# dac-ldo.net
KiCad netlist of a schematic drawn in Altium Designer
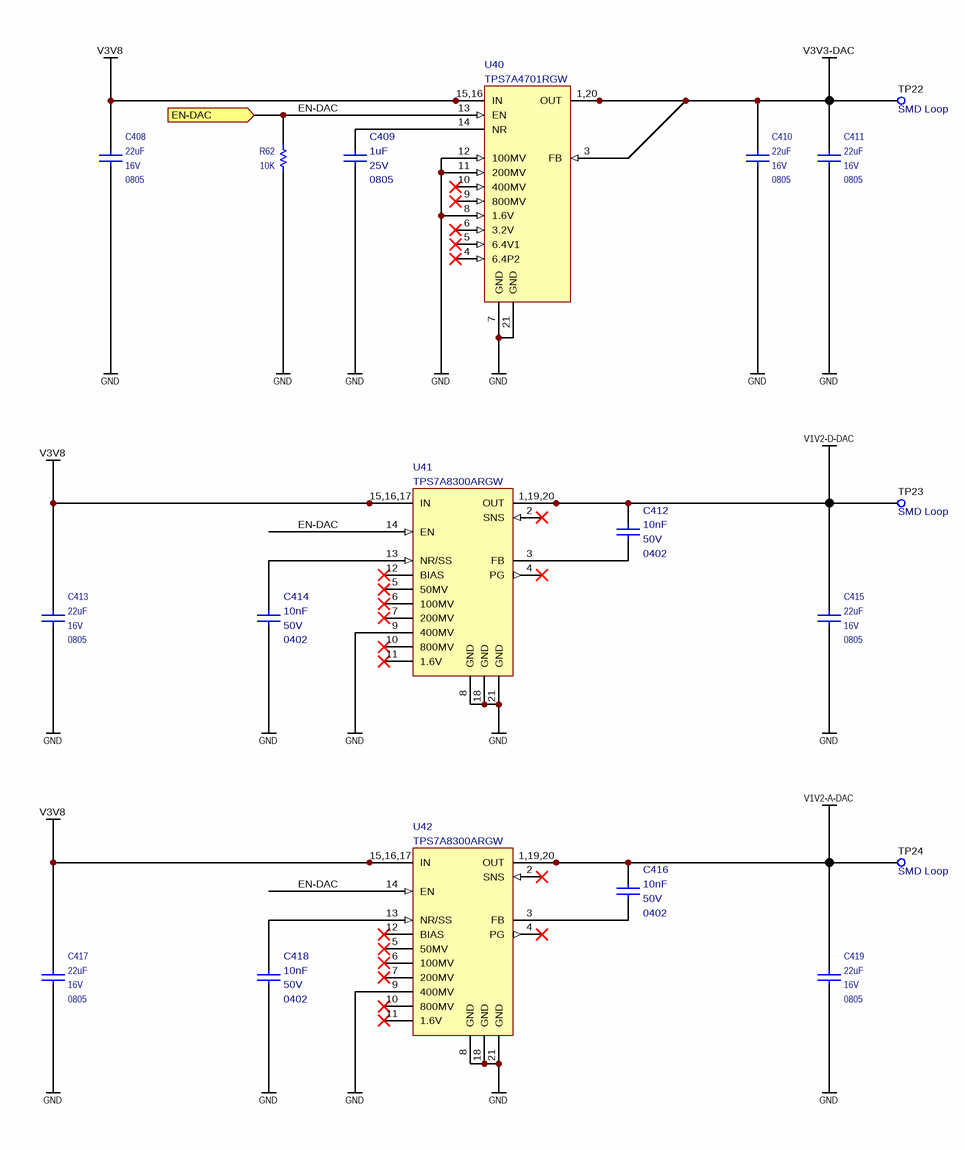
[diagram p0: dac-ldo.SchDoc]

(export (version "E")
  (design (tool "Eeschema 10.0.6"))
  (components
    (comp (ref "C408")
      (value "22uF")
      (footprint "generic:CAPC200X125X145L45N")
      (description "Ceramic Capacitor 22uF ±10% 16V X5R 0805")
      (fields
        (field (name "MANUFACTURER") "Samsung")
        (field (name "VOLTAGE") "16V")
        (field (name "PACKAGE") "0805")
        (field (name "TOLERANCE") "±10%")
      )
      (libsource (lib "generic") (part "CAP 0603"))
    )
    (comp (ref "C409")
      (value "1uF")
      (footprint "CAPC200X125X145L45N")
      (description "Ceramic Capacitor 1uF ±10% 25V X7R 0805")
      (fields
        (field (name "MANUFACTURER") "Taiyo Yuden")
        (field (name "TOLERANCE") "±10%")
        (field (name "PACKAGE") "0805")
        (field (name "VOLTAGE") "25V")
      )
      (libsource (lib "capacitors") (part "CAP"))
    )
    (comp (ref "C410")
      (value "22uF")
      (footprint "generic:CAPC200X125X145L45N")
      (description "Ceramic Capacitor 22uF ±10% 16V X5R 0805")
      (fields
        (field (name "MANUFACTURER") "Samsung")
        (field (name "VOLTAGE") "16V")
        (field (name "PACKAGE") "0805")
        (field (name "TOLERANCE") "±10%")
      )
      (libsource (lib "generic") (part "CAP 0603"))
    )
    (comp (ref "C411")
      (value "22uF")
      (footprint "generic:CAPC200X125X145L45N")
      (description "Ceramic Capacitor 22uF ±10% 16V X5R 0805")
      (fields
        (field (name "MANUFACTURER") "Samsung")
        (field (name "VOLTAGE") "16V")
        (field (name "PACKAGE") "0805")
        (field (name "TOLERANCE") "±10%")
      )
      (libsource (lib "generic") (part "CAP 0603"))
    )
    (comp (ref "C412")
      (value "10nF")
      (footprint "generic:CAPC100X50X55L25N")
      (description "Ceramic Capacitor 10nF ±10% 50V X7R 0402")
      (fields
        (field (name "MANUFACTURER") "Murata")
        (field (name "TOLERANCE") "±10%")
        (field (name "PACKAGE") "0402")
        (field (name "VOLTAGE") "50V")
      )
      (libsource (lib "capacitors") (part "CAP"))
    )
    (comp (ref "C413")
      (value "22uF")
      (footprint "generic:CAPC200X125X145L45N")
      (description "Ceramic Capacitor 22uF ±10% 16V X5R 0805")
      (fields
        (field (name "MANUFACTURER") "Samsung")
        (field (name "VOLTAGE") "16V")
        (field (name "PACKAGE") "0805")
        (field (name "TOLERANCE") "±10%")
      )
      (libsource (lib "generic") (part "CAP 0603"))
    )
    (comp (ref "C414")
      (value "10nF")
      (footprint "generic:CAPC100X50X55L25N")
      (description "Ceramic Capacitor 10nF ±10% 50V X7R 0402")
      (fields
        (field (name "MANUFACTURER") "Murata")
        (field (name "TOLERANCE") "±10%")
        (field (name "PACKAGE") "0402")
        (field (name "VOLTAGE") "50V")
      )
      (libsource (lib "capacitors") (part "CAP"))
    )
    (comp (ref "C415")
      (value "22uF")
      (footprint "generic:CAPC200X125X145L45N")
      (description "Ceramic Capacitor 22uF ±10% 16V X5R 0805")
      (fields
        (field (name "MANUFACTURER") "Samsung")
        (field (name "VOLTAGE") "16V")
        (field (name "PACKAGE") "0805")
        (field (name "TOLERANCE") "±10%")
      )
      (libsource (lib "generic") (part "CAP 0603"))
    )
    (comp (ref "C416")
      (value "10nF")
      (footprint "generic:CAPC100X50X55L25N")
      (description "Ceramic Capacitor 10nF ±10% 50V X7R 0402")
      (fields
        (field (name "MANUFACTURER") "Murata")
        (field (name "TOLERANCE") "±10%")
        (field (name "PACKAGE") "0402")
        (field (name "VOLTAGE") "50V")
      )
      (libsource (lib "capacitors") (part "CAP"))
    )
    (comp (ref "C417")
      (value "22uF")
      (footprint "generic:CAPC200X125X145L45N")
      (description "Ceramic Capacitor 22uF ±10% 16V X5R 0805")
      (fields
        (field (name "MANUFACTURER") "Samsung")
        (field (name "VOLTAGE") "16V")
        (field (name "PACKAGE") "0805")
        (field (name "TOLERANCE") "±10%")
      )
      (libsource (lib "generic") (part "CAP 0603"))
    )
    (comp (ref "C418")
      (value "10nF")
      (footprint "generic:CAPC100X50X55L25N")
      (description "Ceramic Capacitor 10nF ±10% 50V X7R 0402")
      (fields
        (field (name "MANUFACTURER") "Murata")
        (field (name "TOLERANCE") "±10%")
        (field (name "PACKAGE") "0402")
        (field (name "VOLTAGE") "50V")
      )
      (libsource (lib "capacitors") (part "CAP"))
    )
    (comp (ref "C419")
      (value "22uF")
      (footprint "generic:CAPC200X125X145L45N")
      (description "Ceramic Capacitor 22uF ±10% 16V X5R 0805")
      (fields
        (field (name "MANUFACTURER") "Samsung")
        (field (name "VOLTAGE") "16V")
        (field (name "PACKAGE") "0805")
        (field (name "TOLERANCE") "±10%")
      )
      (libsource (lib "generic") (part "CAP 0603"))
    )
    (comp (ref "R62")
      (value "10K")
      (footprint "RESC1005X40N")
      (description "Thick Film Resistor 10k ±1% 0.1W 50V 0402")
      (fields (field (name "MANUFACTURER") "Panasonic") (field (name "TOLERANCE") "±1%"))
      (libsource (lib "Graviton") (part "RES 0402"))
    )
    (comp (ref "TP22")
      (value "5015")
      (footprint "keystone:5015")
      (description "Test Point SMD")
      (fields (field (name "MANUFACTURER") "Keystone") (field (name "NOTES") "SMD Loop"))
      (libsource (lib "generic") (part "TEST_POINT_SMD_50"))
    )
    (comp (ref "TP23")
      (value "5015")
      (footprint "keystone:5015")
      (description "Test Point SMD")
      (fields (field (name "MANUFACTURER") "Keystone") (field (name "NOTES") "SMD Loop"))
      (libsource (lib "generic") (part "TEST_POINT_SMD_50"))
    )
    (comp (ref "TP24")
      (value "5015")
      (footprint "keystone:5015")
      (description "Test Point SMD")
      (fields (field (name "MANUFACTURER") "Keystone") (field (name "NOTES") "SMD Loop"))
      (libsource (lib "generic") (part "TEST_POINT_SMD_50"))
    )
    (comp (ref "U40")
      (value "TPS7A4701RGW")
      (footprint "QFN65P500X500X100-21N")
      (description "Low-Dropout Linear Regulator 20-VQFN")
      (fields (field (name "MANUFACTURER") "Texas Instruments"))
      (libsource (lib "ti") (part "TPS7A4701RGW_1"))
    )
    (comp (ref "U41")
      (value "TPS7A8300ARGW")
      (footprint "texas_instruments:QFN65P500X500X100-21N")
      (description "LDO Regulator, 2A, VQFN-20")
      (fields (field (name "MANUFACTURER") "Texas Instruments"))
      (libsource (lib "ti") (part "TPS7A8300ARGW"))
    )
    (comp (ref "U42")
      (value "TPS7A8300ARGW")
      (footprint "texas_instruments:QFN65P500X500X100-21N")
      (description "LDO Regulator, 2A, VQFN-20")
      (fields (field (name "MANUFACTURER") "Texas Instruments"))
      (libsource (lib "ti") (part "TPS7A8300ARGW"))
    )
  )
  (nets
    (net (code "1") (name "/EN-DAC") (class "Default")
      (node (ref "R62") (pin "1") (pinfunction "1_1") (pintype "passive"))
      (node (ref "U40") (pin "13") (pinfunction "EN_13") (pintype "input"))
      (node (ref "U41") (pin "14") (pinfunction "EN_14") (pintype "input"))
      (node (ref "U42") (pin "14") (pinfunction "EN_14") (pintype "input"))
    )
    (net (code "2") (name "GND") (class "Default")
      (node (ref "C408") (pin "1") (pinfunction "1_1") (pintype "passive"))
      (node (ref "C409") (pin "2") (pinfunction "2_2") (pintype "passive"))
      (node (ref "C410") (pin "1") (pinfunction "1_1") (pintype "passive"))
      (node (ref "C411") (pin "1") (pinfunction "1_1") (pintype "passive"))
      (node (ref "C413") (pin "1") (pinfunction "1_1") (pintype "passive"))
      (node (ref "C414") (pin "2") (pinfunction "2_2") (pintype "passive"))
      (node (ref "C415") (pin "1") (pinfunction "1_1") (pintype "passive"))
      (node (ref "C417") (pin "1") (pinfunction "1_1") (pintype "passive"))
      (node (ref "C418") (pin "2") (pinfunction "2_2") (pintype "passive"))
      (node (ref "C419") (pin "1") (pinfunction "1_1") (pintype "passive"))
      (node (ref "R62") (pin "2") (pinfunction "2_2") (pintype "passive"))
      (node (ref "U40") (pin "11") (pinfunction "200MV_11") (pintype "input"))
      (node (ref "U40") (pin "12") (pinfunction "100MV_12") (pintype "input"))
      (node (ref "U40") (pin "21") (pinfunction "GND_21") (pintype "power_in"))
      (node (ref "U40") (pin "7") (pinfunction "GND_7") (pintype "power_in"))
      (node (ref "U40") (pin "8") (pinfunction "1.6V_8") (pintype "input"))
      (node (ref "U41") (pin "18") (pinfunction "GND_18") (pintype "passive"))
      (node (ref "U41") (pin "21") (pinfunction "GND_21") (pintype "passive"))
      (node (ref "U41") (pin "8") (pinfunction "GND_8") (pintype "passive"))
      (node (ref "U41") (pin "9") (pinfunction "400MV_9") (pintype "passive"))
      (node (ref "U42") (pin "18") (pinfunction "GND_18") (pintype "passive"))
      (node (ref "U42") (pin "21") (pinfunction "GND_21") (pintype "passive"))
      (node (ref "U42") (pin "8") (pinfunction "GND_8") (pintype "passive"))
      (node (ref "U42") (pin "9") (pinfunction "400MV_9") (pintype "passive"))
    )
    (net (code "3") (name "Net-(U40-NR)") (class "Default")
      (node (ref "C409") (pin "1") (pinfunction "1_1") (pintype "passive"))
      (node (ref "U40") (pin "14") (pinfunction "NR_14") (pintype "passive"))
    )
    (net (code "4") (name "Net-(U41-FB)") (class "Default")
      (node (ref "C412") (pin "2") (pinfunction "2_2") (pintype "passive"))
      (node (ref "U41") (pin "3") (pinfunction "FB_3") (pintype "passive"))
    )
    (net (code "5") (name "Net-(U41-NR{slash}SS)") (class "Default")
      (node (ref "C414") (pin "1") (pinfunction "1_1") (pintype "passive"))
      (node (ref "U41") (pin "13") (pinfunction "NR/SS_13") (pintype "input"))
    )
    (net (code "6") (name "Net-(U42-FB)") (class "Default")
      (node (ref "C416") (pin "2") (pinfunction "2_2") (pintype "passive"))
      (node (ref "U42") (pin "3") (pinfunction "FB_3") (pintype "passive"))
    )
    (net (code "7") (name "Net-(U42-NR{slash}SS)") (class "Default")
      (node (ref "C418") (pin "1") (pinfunction "1_1") (pintype "passive"))
      (node (ref "U42") (pin "13") (pinfunction "NR/SS_13") (pintype "input"))
    )
    (net (code "8") (name "V1V2-A-DAC") (class "Default")
      (node (ref "C416") (pin "1") (pinfunction "1_1") (pintype "passive"))
      (node (ref "C419") (pin "2") (pinfunction "2_2") (pintype "passive"))
      (node (ref "TP24") (pin "1") (pinfunction "1_1") (pintype "passive"))
      (node (ref "U42") (pin "1") (pinfunction "OUT_1") (pintype "passive"))
      (node (ref "U42") (pin "19") (pinfunction "OUT_19") (pintype "passive"))
      (node (ref "U42") (pin "20") (pinfunction "OUT_20") (pintype "passive"))
    )
    (net (code "9") (name "V1V2-D-DAC") (class "Default")
      (node (ref "C412") (pin "1") (pinfunction "1_1") (pintype "passive"))
      (node (ref "C415") (pin "2") (pinfunction "2_2") (pintype "passive"))
      (node (ref "TP23") (pin "1") (pinfunction "1_1") (pintype "passive"))
      (node (ref "U41") (pin "1") (pinfunction "OUT_1") (pintype "passive"))
      (node (ref "U41") (pin "19") (pinfunction "OUT_19") (pintype "passive"))
      (node (ref "U41") (pin "20") (pinfunction "OUT_20") (pintype "passive"))
    )
    (net (code "10") (name "V3V3-DAC") (class "Default")
      (node (ref "C410") (pin "2") (pinfunction "2_2") (pintype "passive"))
      (node (ref "C411") (pin "2") (pinfunction "2_2") (pintype "passive"))
      (node (ref "TP22") (pin "1") (pinfunction "1_1") (pintype "passive"))
      (node (ref "U40") (pin "1") (pinfunction "OUT_1") (pintype "passive"))
      (node (ref "U40") (pin "20") (pinfunction "OUT_20") (pintype "passive"))
      (node (ref "U40") (pin "3") (pinfunction "FB_3") (pintype "input"))
    )
    (net (code "11") (name "V3V8") (class "Default")
      (node (ref "C408") (pin "2") (pinfunction "2_2") (pintype "passive"))
      (node (ref "C413") (pin "2") (pinfunction "2_2") (pintype "passive"))
      (node (ref "C417") (pin "2") (pinfunction "2_2") (pintype "passive"))
      (node (ref "U40") (pin "15") (pinfunction "IN_15") (pintype "passive"))
      (node (ref "U40") (pin "16") (pinfunction "IN_16") (pintype "passive"))
      (node (ref "U41") (pin "15") (pinfunction "IN_15") (pintype "passive"))
      (node (ref "U41") (pin "16") (pinfunction "IN_16") (pintype "passive"))
      (node (ref "U41") (pin "17") (pinfunction "IN_17") (pintype "passive"))
      (node (ref "U42") (pin "15") (pinfunction "IN_15") (pintype "passive"))
      (node (ref "U42") (pin "16") (pinfunction "IN_16") (pintype "passive"))
      (node (ref "U42") (pin "17") (pinfunction "IN_17") (pintype "passive"))
    )
    (net (code "12") (name "unconnected-(U40-3.2V-Pad6)") (class "Default")
      (node (ref "U40") (pin "6") (pinfunction "3.2V_6") (pintype "input+no_connect"))
    )
    (net (code "13") (name "unconnected-(U40-6.4P2-Pad4)") (class "Default")
      (node (ref "U40") (pin "4") (pinfunction "6.4P2_4") (pintype "input+no_connect"))
    )
    (net (code "14") (name "unconnected-(U40-6.4V1-Pad5)") (class "Default")
      (node (ref "U40") (pin "5") (pinfunction "6.4V1_5") (pintype "input+no_connect"))
    )
    (net (code "15") (name "unconnected-(U40-400MV-Pad10)") (class "Default")
      (node (ref "U40") (pin "10") (pinfunction "400MV_10") (pintype "input+no_connect"))
    )
    (net (code "16") (name "unconnected-(U40-800MV-Pad9)") (class "Default")
      (node (ref "U40") (pin "9") (pinfunction "800MV_9") (pintype "input+no_connect"))
    )
    (net (code "17") (name "unconnected-(U41-1.6V-Pad11)") (class "Default")
      (node (ref "U41") (pin "11") (pinfunction "1.6V_11") (pintype "passive+no_connect"))
    )
    (net (code "18") (name "unconnected-(U41-50MV-Pad5)") (class "Default")
      (node (ref "U41") (pin "5") (pinfunction "50MV_5") (pintype "passive+no_connect"))
    )
    (net (code "19") (name "unconnected-(U41-100MV-Pad6)") (class "Default")
      (node (ref "U41") (pin "6") (pinfunction "100MV_6") (pintype "passive+no_connect"))
    )
    (net (code "20") (name "unconnected-(U41-200MV-Pad7)") (class "Default")
      (node (ref "U41") (pin "7") (pinfunction "200MV_7") (pintype "passive+no_connect"))
    )
    (net (code "21") (name "unconnected-(U41-800MV-Pad10)") (class "Default")
      (node (ref "U41") (pin "10") (pinfunction "800MV_10") (pintype "passive+no_connect"))
    )
    (net (code "22") (name "unconnected-(U41-BIAS-Pad12)") (class "Default")
      (node (ref "U41") (pin "12") (pinfunction "BIAS_12") (pintype "power_in+no_connect"))
    )
    (net (code "23") (name "unconnected-(U41-PG-Pad4)") (class "Default")
      (node (ref "U41") (pin "4") (pinfunction "PG_4") (pintype "output+no_connect"))
    )
    (net (code "24") (name "unconnected-(U41-SNS-Pad2)") (class "Default")
      (node (ref "U41") (pin "2") (pinfunction "SNS_2") (pintype "input+no_connect"))
    )
    (net (code "25") (name "unconnected-(U42-1.6V-Pad11)") (class "Default")
      (node (ref "U42") (pin "11") (pinfunction "1.6V_11") (pintype "passive+no_connect"))
    )
    (net (code "26") (name "unconnected-(U42-50MV-Pad5)") (class "Default")
      (node (ref "U42") (pin "5") (pinfunction "50MV_5") (pintype "passive+no_connect"))
    )
    (net (code "27") (name "unconnected-(U42-100MV-Pad6)") (class "Default")
      (node (ref "U42") (pin "6") (pinfunction "100MV_6") (pintype "passive+no_connect"))
    )
    (net (code "28") (name "unconnected-(U42-200MV-Pad7)") (class "Default")
      (node (ref "U42") (pin "7") (pinfunction "200MV_7") (pintype "passive+no_connect"))
    )
    (net (code "29") (name "unconnected-(U42-800MV-Pad10)") (class "Default")
      (node (ref "U42") (pin "10") (pinfunction "800MV_10") (pintype "passive+no_connect"))
    )
    (net (code "30") (name "unconnected-(U42-BIAS-Pad12)") (class "Default")
      (node (ref "U42") (pin "12") (pinfunction "BIAS_12") (pintype "power_in+no_connect"))
    )
    (net (code "31") (name "unconnected-(U42-PG-Pad4)") (class "Default")
      (node (ref "U42") (pin "4") (pinfunction "PG_4") (pintype "output+no_connect"))
    )
    (net (code "32") (name "unconnected-(U42-SNS-Pad2)") (class "Default")
      (node (ref "U42") (pin "2") (pinfunction "SNS_2") (pintype "input+no_connect"))
    )
  )
)
